# supply.net
KiCad netlist of a schematic drawn in Altium Designer
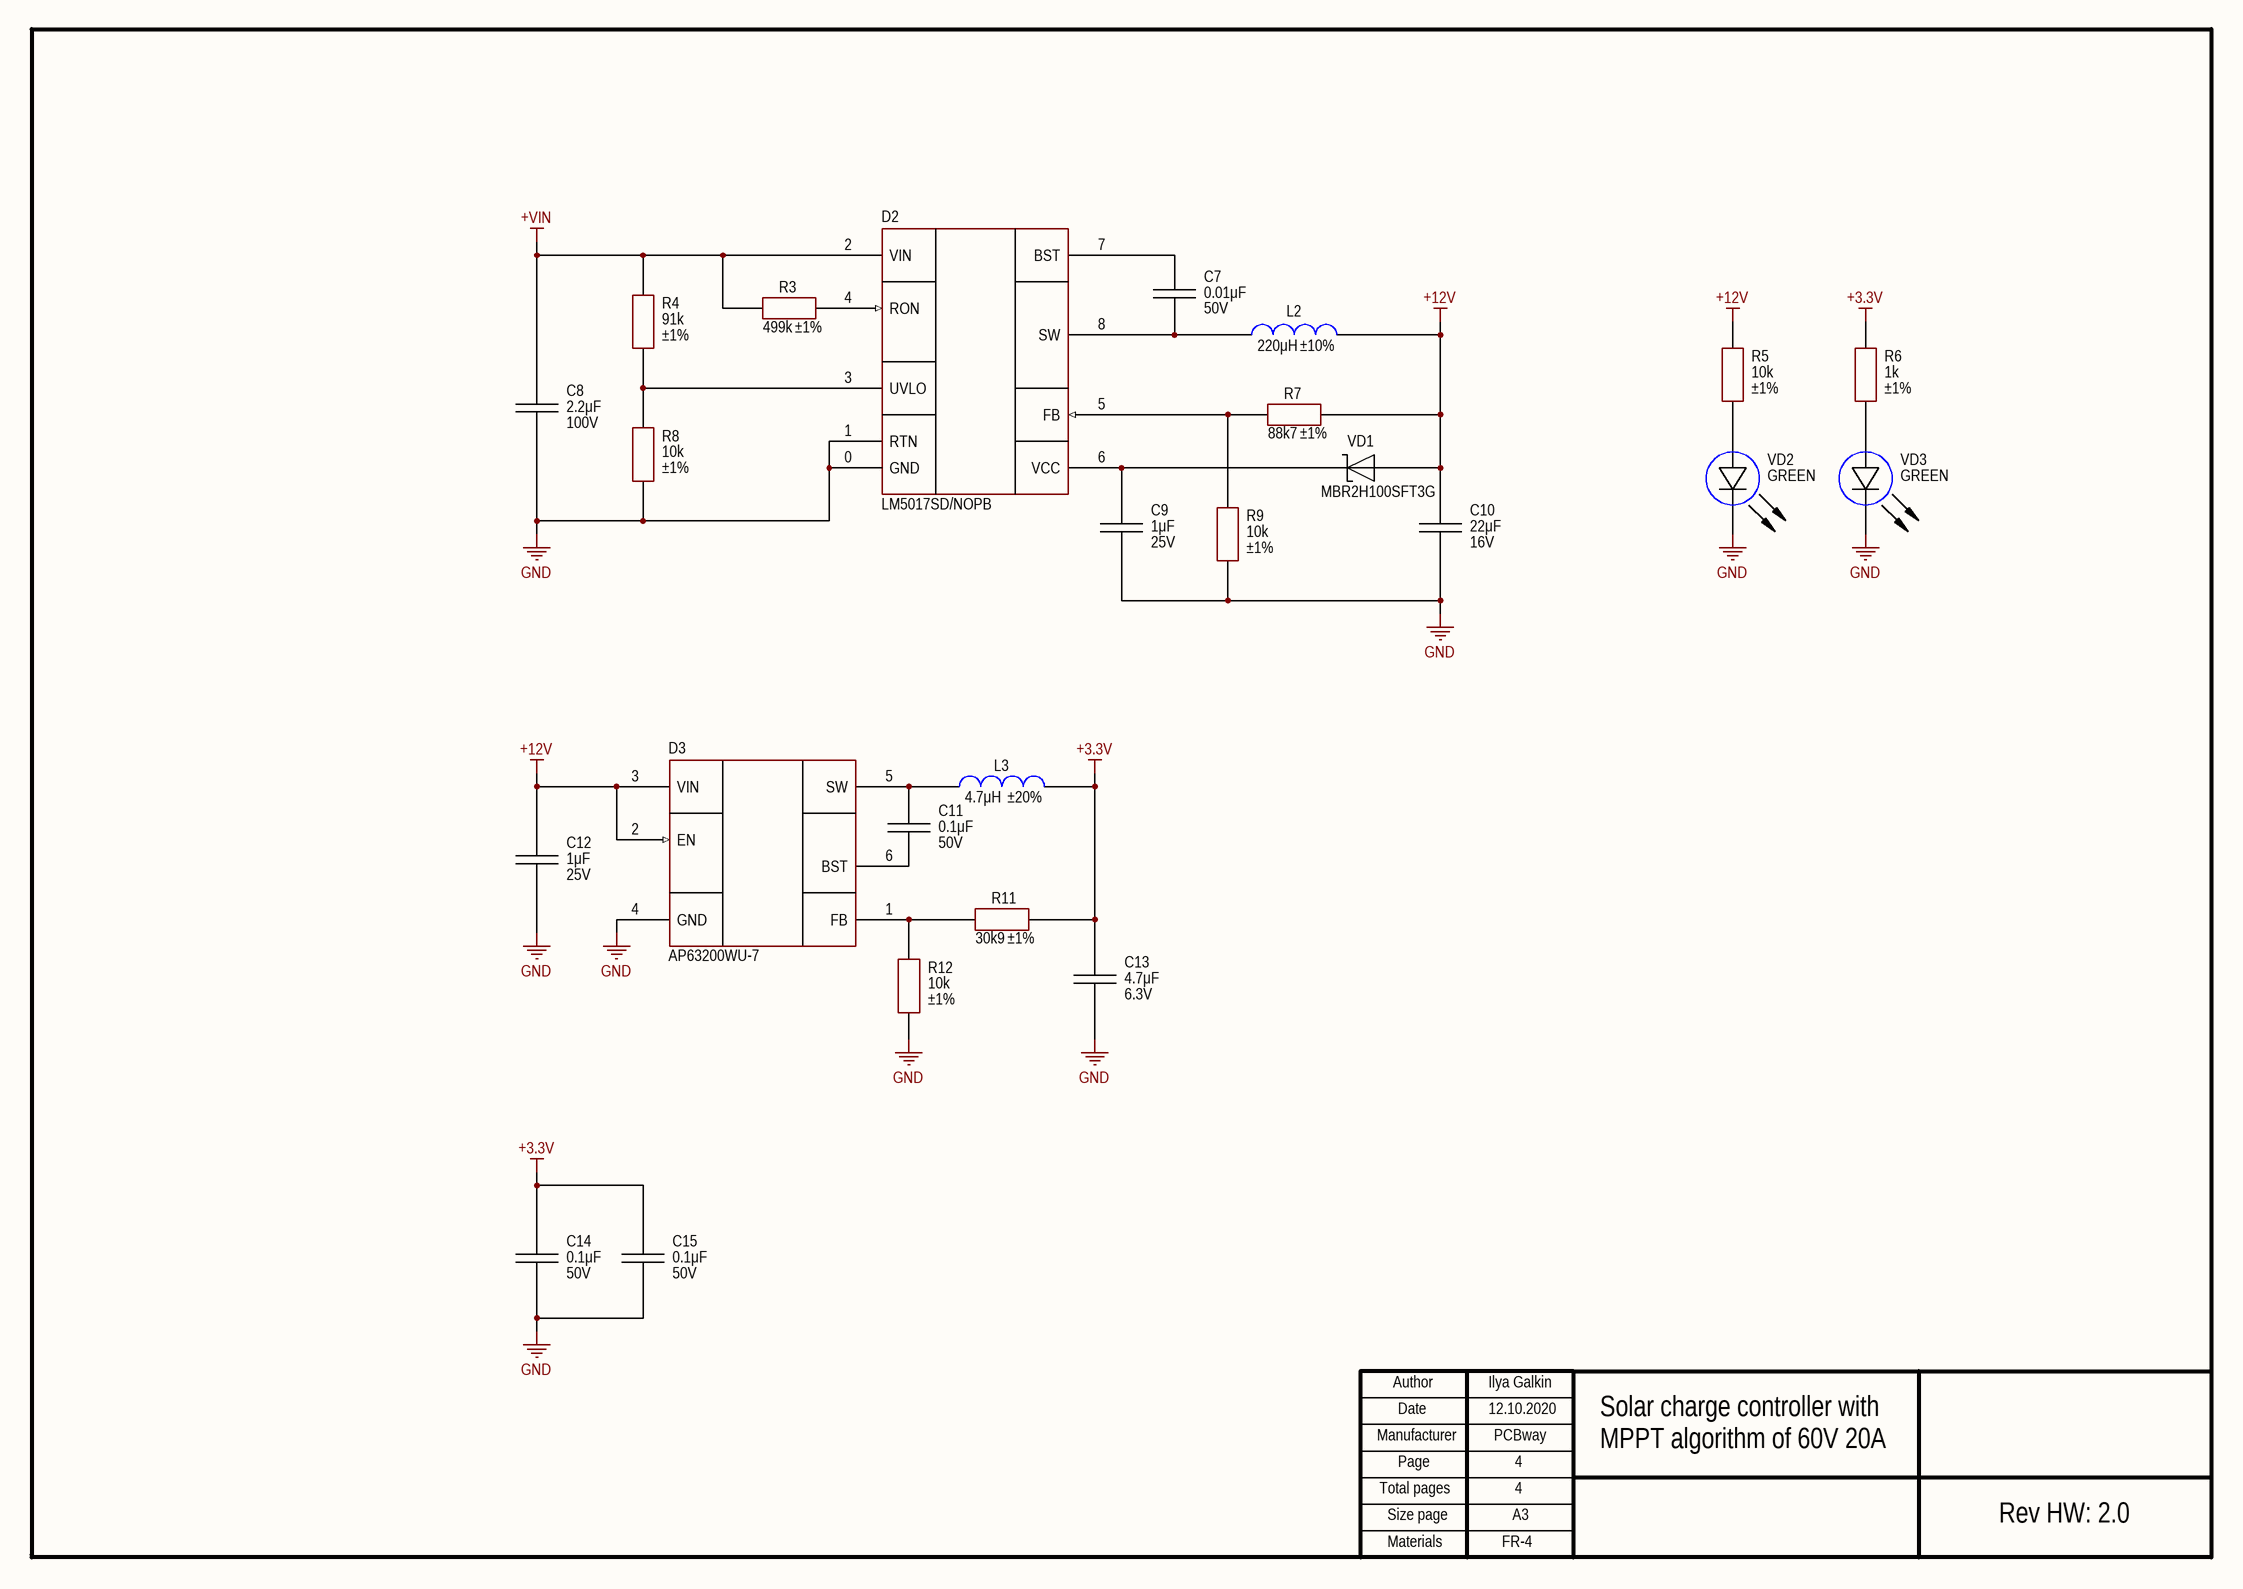
[diagram p0: supply.SchDoc]

(export (version "E")
  (design (tool "Eeschema 10.0.6"))
  (components
    (comp (ref "C7")
      (value "0.01μF")
      (footprint "CAP: 0603")
      (fields
        (field (name "MANUFACTURER") "Samsung")
        (field (name "PARTNUMBER") "CL10B103KB8NNNC")
        (field (name "VALUEMANUFACTURERPARTNUMBER") "Ceramic capacitor, 0.01μF, X7R, ±10%, 50V, 0603, -55...+125°C")
        (field (name "VOLTAGE") "50V")
      )
      (libsource (lib "Capacitor") (part "Ceramic_0603"))
    )
    (comp (ref "C8")
      (value "2.2μF")
      (footprint "CAP: 1210")
      (fields
        (field (name "MANUFACTURER") "Samsung")
        (field (name "PARTNUMBER") "CL32B225KCJSNNE")
        (field (name "VALUEMANUFACTURERPARTNUMBER") "Ceramic capacitor, 2.2μF, X7R, ±10%, 100V, 1210, -55...+125°C")
        (field (name "VOLTAGE") "100V")
      )
      (libsource (lib "capacitor") (part "Ceramic_1210"))
    )
    (comp (ref "C9")
      (value "1μF")
      (footprint "CAP: 0603")
      (fields
        (field (name "MANUFACTURER") "Samsung")
        (field (name "PARTNUMBER") "CL10B105KA8NNNC")
        (field (name "VALUEMANUFACTURERPARTNUMBER") "Ceramic capacitor, 1μF, X7R, ±10%, 25V, 0603, -55...+125°C")
        (field (name "VOLTAGE") "25V")
      )
      (libsource (lib "Capacitor") (part "Ceramic_0603"))
    )
    (comp (ref "C10")
      (value "22μF")
      (footprint "CAP: 1210")
      (fields
        (field (name "MANUFACTURER") "Samsung")
        (field (name "PARTNUMBER") "CL32B226KOJNNNE")
        (field (name "VALUEMANUFACTURERPARTNUMBER") "Ceramic capacitor, 22μF, X7R, ±10%, 16V, 1210, -55...+125°C")
        (field (name "VOLTAGE") "16V")
      )
      (libsource (lib "capacitor") (part "Ceramic_1210"))
    )
    (comp (ref "C11")
      (value "0.1μF")
      (footprint "CAP: 0603")
      (fields
        (field (name "MANUFACTURER") "Samsung")
        (field (name "PARTNUMBER") "CL10B104KB8WPND")
        (field (name "VALUEMANUFACTURERPARTNUMBER") "Ceramic capacitor, 0.1μF, X7R, ±10%, 50V, 0603, -55...+125°C")
        (field (name "VOLTAGE") "50V")
      )
      (libsource (lib "Capacitor") (part "Ceramic_0603"))
    )
    (comp (ref "C12")
      (value "1μF")
      (footprint "CAP: 0603")
      (fields
        (field (name "MANUFACTURER") "Samsung")
        (field (name "PARTNUMBER") "CL10B105KA8NNNC")
        (field (name "VALUEMANUFACTURERPARTNUMBER") "Ceramic capacitor, 1μF, X7R, ±10%, 25V, 0603, -55...+125°C")
        (field (name "VOLTAGE") "25V")
      )
      (libsource (lib "Capacitor") (part "Ceramic_0603"))
    )
    (comp (ref "C13")
      (value "4.7μF")
      (footprint "CAP: 0603")
      (fields
        (field (name "MANUFACTURER") "Samsung")
        (field (name "PARTNUMBER") "CL10B475KQ8NQNC")
        (field (name "VALUEMANUFACTURERPARTNUMBER") "Ceramic capacitor, 4.7μF, X7R, ±10%, 6.3V, 0603, -55...+125°C")
        (field (name "VOLTAGE") "6.3V")
      )
      (libsource (lib "Capacitor") (part "Ceramic_0603"))
    )
    (comp (ref "C14")
      (value "0.1μF")
      (footprint "CAP: 0603")
      (fields
        (field (name "MANUFACTURER") "Samsung")
        (field (name "PARTNUMBER") "CL10B104KB8WPND")
        (field (name "VALUEMANUFACTURERPARTNUMBER") "Ceramic capacitor, 0.1μF, X7R, ±10%, 50V, 0603, -55...+125°C")
        (field (name "VOLTAGE") "50V")
      )
      (libsource (lib "Capacitor") (part "Ceramic_0603"))
    )
    (comp (ref "C15")
      (value "0.1μF")
      (footprint "CAP: 0603")
      (fields
        (field (name "MANUFACTURER") "Samsung")
        (field (name "PARTNUMBER") "CL10B104KB8WPND")
        (field (name "VALUEMANUFACTURERPARTNUMBER") "Ceramic capacitor, 0.1μF, X7R, ±10%, 50V, 0603, -55...+125°C")
        (field (name "VOLTAGE") "50V")
      )
      (libsource (lib "Capacitor") (part "Ceramic_0603"))
    )
    (comp (ref "D2")
      (value "~")
      (footprint "8-WSON (4x4)")
      (description "Buck converter")
      (fields
        (field (name "MANUFACTURER") "Texas Instruments")
        (field (name "VALUEMANUFACTURERPARTNUMBER") "DC/DC buck converter, input 7.5...100V, 1MHz, output 1.225...90V, 0.6A, -40...+125°C, 8-WSON")
        (field (name "PARTNUMBER") "LM5017SD/NOPB")
      )
      (libsource (lib "ic-power-supply") (part "LM5017SD"))
    )
    (comp (ref "D3")
      (value "~")
      (footprint "SOT23-6")
      (description "Buck converter")
      (fields
        (field (name "MANUFACTURER") "Diodes")
        (field (name "VALUEMANUFACTURERPARTNUMBER") "DC/DC buck converter, input 3.8...32V, 500kHz, output 1.2...12V, 2A, -40...+85°C, SOT23-6")
        (field (name "PARTNUMBER") "AP63200WU-7")
      )
      (libsource (lib "ic-power-supply") (part "AP63200WU-7"))
    )
    (comp (ref "L2")
      (value "220μH")
      (footprint "IND: SDR0805")
      (fields
        (field (name "MANUFACTURER") "Bourns")
        (field (name "PARTNUMBER") "SDR0805-221KL")
        (field (name "VALUEMANUFACTURERPARTNUMBER") "Fixed inductor, 220μH, ±10%, SDR0805, 490mA, -40...+125°C")
        (field (name "TOLERANCE") "±10%")
      )
      (libsource (lib "Inductor") (part "Inductor_SDR0805"))
    )
    (comp (ref "L3")
      (value "4.7μH")
      (footprint "IND: CD32")
      (fields
        (field (name "MANUFACTURER") "YJYCOIN")
        (field (name "PARTNUMBER") "CD32YP0302-4R7M")
        (field (name "VALUEMANUFACTURERPARTNUMBER") "Fixed inductor, 4.7μH, ±20%, CD32 series, 1.5A, -40...+125°C")
        (field (name "TOLERANCE") "±20%")
      )
      (libsource (lib "inductor") (part "Inductor_CD32"))
    )
    (comp (ref "R3")
      (value "499k")
      (footprint "RES: 0603")
      (fields
        (field (name "MANUFACTURER") "Yageo")
        (field (name "PARTNUMBER") "RC0603FR-07499KL")
        (field (name "VALUEMANUFACTURERPARTNUMBER") "Resistor film, 499k, ±1%, 0603, 0.1W, -55...+125°C")
        (field (name "TOLERANCE") "±1%")
      )
      (libsource (lib "Resistor") (part "Resistor_0603"))
    )
    (comp (ref "R4")
      (value "91k")
      (footprint "RES: 0603")
      (fields
        (field (name "MANUFACTURER") "Yageo")
        (field (name "PARTNUMBER") "RC0603FR-0791KL")
        (field (name "VALUEMANUFACTURERPARTNUMBER") "Resistor film, 91k, ±1%, 0603, 0.1W, -55...+125°C")
        (field (name "TOLERANCE") "±1%")
      )
      (libsource (lib "") (part "Resistor_0603_1"))
    )
    (comp (ref "R5")
      (value "10k")
      (footprint "RES: 0603")
      (fields
        (field (name "MANUFACTURER") "Yageo")
        (field (name "PARTNUMBER") "AC0603FR-0710KL")
        (field (name "VALUEMANUFACTURERPARTNUMBER") "Resistor film, 10k, ±1%, 0603, 0.1W, -55...+125°C")
        (field (name "TOLERANCE") "±1%")
      )
      (libsource (lib "") (part "Resistor_0603_1"))
    )
    (comp (ref "R6")
      (value "1k")
      (footprint "RES: 0603")
      (fields
        (field (name "MANUFACTURER") "Yageo")
        (field (name "PARTNUMBER") "RC0603FR-071KL")
        (field (name "VALUEMANUFACTURERPARTNUMBER") "Resistor film, 1k, ±1%, 0603, 0.1W, -55...+125°C")
        (field (name "TOLERANCE") "±1%")
      )
      (libsource (lib "") (part "Resistor_0603_1"))
    )
    (comp (ref "R7")
      (value "88k7")
      (footprint "RES: 0603")
      (fields
        (field (name "MANUFACTURER") "Yageo")
        (field (name "PARTNUMBER") "RC0603FR-0788K7L")
        (field (name "VALUEMANUFACTURERPARTNUMBER") "Resistor film, 88k7, ±1%, 0603, 0.1W, -55...+125°C")
        (field (name "TOLERANCE") "±1%")
      )
      (libsource (lib "Resistor") (part "Resistor_0603"))
    )
    (comp (ref "R8")
      (value "10k")
      (footprint "RES: 0603")
      (fields
        (field (name "MANUFACTURER") "Yageo")
        (field (name "PARTNUMBER") "AC0603FR-0710KL")
        (field (name "VALUEMANUFACTURERPARTNUMBER") "Resistor film, 10k, ±1%, 0603, 0.1W, -55...+125°C")
        (field (name "TOLERANCE") "±1%")
      )
      (libsource (lib "") (part "Resistor_0603_1"))
    )
    (comp (ref "R9")
      (value "10k")
      (footprint "RES: 0603")
      (fields
        (field (name "MANUFACTURER") "Yageo")
        (field (name "PARTNUMBER") "AC0603FR-0710KL")
        (field (name "VALUEMANUFACTURERPARTNUMBER") "Resistor film, 10k, ±1%, 0603, 0.1W, -55...+125°C")
        (field (name "TOLERANCE") "±1%")
      )
      (libsource (lib "") (part "Resistor_0603_1"))
    )
    (comp (ref "R11")
      (value "30k9")
      (footprint "RES: 0603")
      (fields
        (field (name "MANUFACTURER") "Yageo")
        (field (name "PARTNUMBER") "RC0603FR-0730K9L")
        (field (name "VALUEMANUFACTURERPARTNUMBER") "Resistor film, 30k9, ±1%, 0603, 0.1W, -55...+125°C")
        (field (name "TOLERANCE") "±1%")
      )
      (libsource (lib "Resistor") (part "Resistor_0603"))
    )
    (comp (ref "R12")
      (value "10k")
      (footprint "RES: 0603")
      (fields
        (field (name "MANUFACTURER") "Yageo")
        (field (name "PARTNUMBER") "AC0603FR-0710KL")
        (field (name "VALUEMANUFACTURERPARTNUMBER") "Resistor film, 10k, ±1%, 0603, 0.1W, -55...+125°C")
        (field (name "TOLERANCE") "±1%")
      )
      (libsource (lib "") (part "Resistor_0603_1"))
    )
    (comp (ref "VD1")
      (value "~")
      (footprint "DIODE: SOD123F")
      (fields
        (field (name "MANUFACTURER") "ON Semiconductor")
        (field (name "VALUEMANUFACTURERPARTNUMBER") "Schottky diode, 100V, 2A, 840mV, 15pF, SOD-123F, -55...+150°C")
        (field (name "VOLTAGE") "100V")
        (field (name "PARTNUMBER") "MBR2H100SFT3G")
      )
      (libsource (lib "Diode") (part "Schottky_single"))
    )
    (comp (ref "VD2")
      (value "~")
      (footprint "LED: 0603G")
      (fields
        (field (name "MANUFACTURER") "Wurth")
        (field (name "VALUEMANUFACTURERPARTNUMBER") "LED, 20mA, 2V, 0603, -55...+150°C")
        (field (name "PARTNUMBER") "150060VS75000")
        (field (name "COLOR") "GREEN")
      )
      (libsource (lib "Diode") (part "LED_single"))
    )
    (comp (ref "VD3")
      (value "~")
      (footprint "LED: 0603G")
      (fields
        (field (name "MANUFACTURER") "Wurth")
        (field (name "VALUEMANUFACTURERPARTNUMBER") "LED, 20mA, 2V, 0603, -55...+150°C")
        (field (name "PARTNUMBER") "150060VS75000")
        (field (name "COLOR") "GREEN")
      )
      (libsource (lib "Diode") (part "LED_single"))
    )
  )
  (nets
    (net (code "1") (name "+3.3V") (class "Default")
      (node (ref "C13") (pin "2") (pinfunction "2_2") (pintype "power_in"))
      (node (ref "C14") (pin "2") (pinfunction "2_2") (pintype "power_in"))
      (node (ref "C15") (pin "2") (pinfunction "2_2") (pintype "power_in"))
      (node (ref "L3") (pin "1") (pinfunction "1_1") (pintype "passive"))
      (node (ref "R11") (pin "1") (pinfunction "1_1") (pintype "passive"))
      (node (ref "R6") (pin "2") (pinfunction "2_2") (pintype "passive"))
    )
    (net (code "2") (name "+12V") (class "Default")
      (node (ref "C10") (pin "2") (pinfunction "2_2") (pintype "passive"))
      (node (ref "C12") (pin "2") (pinfunction "2_2") (pintype "power_in"))
      (node (ref "D3") (pin "2") (pinfunction "EN_2") (pintype "input"))
      (node (ref "D3") (pin "3") (pinfunction "VIN_3") (pintype "passive"))
      (node (ref "L2") (pin "1") (pinfunction "1_1") (pintype "passive"))
      (node (ref "R5") (pin "2") (pinfunction "2_2") (pintype "passive"))
      (node (ref "R7") (pin "1") (pinfunction "1_1") (pintype "passive"))
      (node (ref "VD1") (pin "1") (pinfunction "1_1") (pintype "passive"))
    )
    (net (code "3") (name "+VIN") (class "Default")
      (node (ref "C8") (pin "2") (pinfunction "2_2") (pintype "passive"))
      (node (ref "D2") (pin "2") (pinfunction "VIN_2") (pintype "passive"))
      (node (ref "R3") (pin "2") (pinfunction "2_2") (pintype "passive"))
      (node (ref "R4") (pin "2") (pinfunction "2_2") (pintype "passive"))
    )
    (net (code "4") (name "GND") (class "Default")
      (node (ref "C10") (pin "1") (pinfunction "1_1") (pintype "passive"))
      (node (ref "C12") (pin "1") (pinfunction "1_1") (pintype "power_in"))
      (node (ref "C13") (pin "1") (pinfunction "1_1") (pintype "power_in"))
      (node (ref "C14") (pin "1") (pinfunction "1_1") (pintype "power_in"))
      (node (ref "C15") (pin "1") (pinfunction "1_1") (pintype "power_in"))
      (node (ref "C8") (pin "1") (pinfunction "1_1") (pintype "passive"))
      (node (ref "C9") (pin "1") (pinfunction "1_1") (pintype "power_in"))
      (node (ref "D2") (pin "0") (pinfunction "GND_0") (pintype "passive"))
      (node (ref "D2") (pin "1") (pinfunction "RTN_1") (pintype "passive"))
      (node (ref "D3") (pin "4") (pinfunction "GND_4") (pintype "passive"))
      (node (ref "R12") (pin "1") (pinfunction "1_1") (pintype "passive"))
      (node (ref "R8") (pin "1") (pinfunction "1_1") (pintype "passive"))
      (node (ref "R9") (pin "1") (pinfunction "1_1") (pintype "passive"))
      (node (ref "VD2") (pin "2") (pinfunction "C_2") (pintype "passive"))
      (node (ref "VD3") (pin "2") (pinfunction "C_2") (pintype "passive"))
    )
    (net (code "5") (name "Net-(D2-BST)") (class "Default")
      (node (ref "C7") (pin "2") (pinfunction "2_2") (pintype "power_in"))
      (node (ref "D2") (pin "7") (pinfunction "BST_7") (pintype "passive"))
    )
    (net (code "6") (name "Net-(D2-FB)") (class "Default")
      (node (ref "D2") (pin "5") (pinfunction "FB_5") (pintype "input"))
      (node (ref "R7") (pin "2") (pinfunction "2_2") (pintype "passive"))
      (node (ref "R9") (pin "2") (pinfunction "2_2") (pintype "passive"))
    )
    (net (code "7") (name "Net-(D2-RON)") (class "Default")
      (node (ref "D2") (pin "4") (pinfunction "RON_4") (pintype "input"))
      (node (ref "R3") (pin "1") (pinfunction "1_1") (pintype "passive"))
    )
    (net (code "8") (name "Net-(D2-SW)") (class "Default")
      (node (ref "C7") (pin "1") (pinfunction "1_1") (pintype "power_in"))
      (node (ref "D2") (pin "8") (pinfunction "SW_8") (pintype "passive"))
      (node (ref "L2") (pin "2") (pinfunction "2_2") (pintype "passive"))
    )
    (net (code "9") (name "Net-(D2-UVLO)") (class "Default")
      (node (ref "D2") (pin "3") (pinfunction "UVLO_3") (pintype "passive"))
      (node (ref "R4") (pin "1") (pinfunction "1_1") (pintype "passive"))
      (node (ref "R8") (pin "2") (pinfunction "2_2") (pintype "passive"))
    )
    (net (code "10") (name "Net-(D2-VCC)") (class "Default")
      (node (ref "C9") (pin "2") (pinfunction "2_2") (pintype "power_in"))
      (node (ref "D2") (pin "6") (pinfunction "VCC_6") (pintype "passive"))
      (node (ref "VD1") (pin "2") (pinfunction "2_2") (pintype "passive"))
    )
    (net (code "11") (name "Net-(D3-BST)") (class "Default")
      (node (ref "C11") (pin "1") (pinfunction "1_1") (pintype "power_in"))
      (node (ref "D3") (pin "6") (pinfunction "BST_6") (pintype "passive"))
    )
    (net (code "12") (name "Net-(D3-FB)") (class "Default")
      (node (ref "D3") (pin "1") (pinfunction "FB_1") (pintype "passive"))
      (node (ref "R11") (pin "2") (pinfunction "2_2") (pintype "passive"))
      (node (ref "R12") (pin "2") (pinfunction "2_2") (pintype "passive"))
    )
    (net (code "13") (name "Net-(D3-SW)") (class "Default")
      (node (ref "C11") (pin "2") (pinfunction "2_2") (pintype "power_in"))
      (node (ref "D3") (pin "5") (pinfunction "SW_5") (pintype "passive"))
      (node (ref "L3") (pin "2") (pinfunction "2_2") (pintype "passive"))
    )
    (net (code "14") (name "Net-(VD2-A)") (class "Default")
      (node (ref "R5") (pin "1") (pinfunction "1_1") (pintype "passive"))
      (node (ref "VD2") (pin "1") (pinfunction "A_1") (pintype "passive"))
    )
    (net (code "15") (name "Net-(VD3-A)") (class "Default")
      (node (ref "R6") (pin "1") (pinfunction "1_1") (pintype "passive"))
      (node (ref "VD3") (pin "1") (pinfunction "A_1") (pintype "passive"))
    )
  )
)
